# Irrigatron.net
KiCad netlist of a schematic drawn in EasyEDA
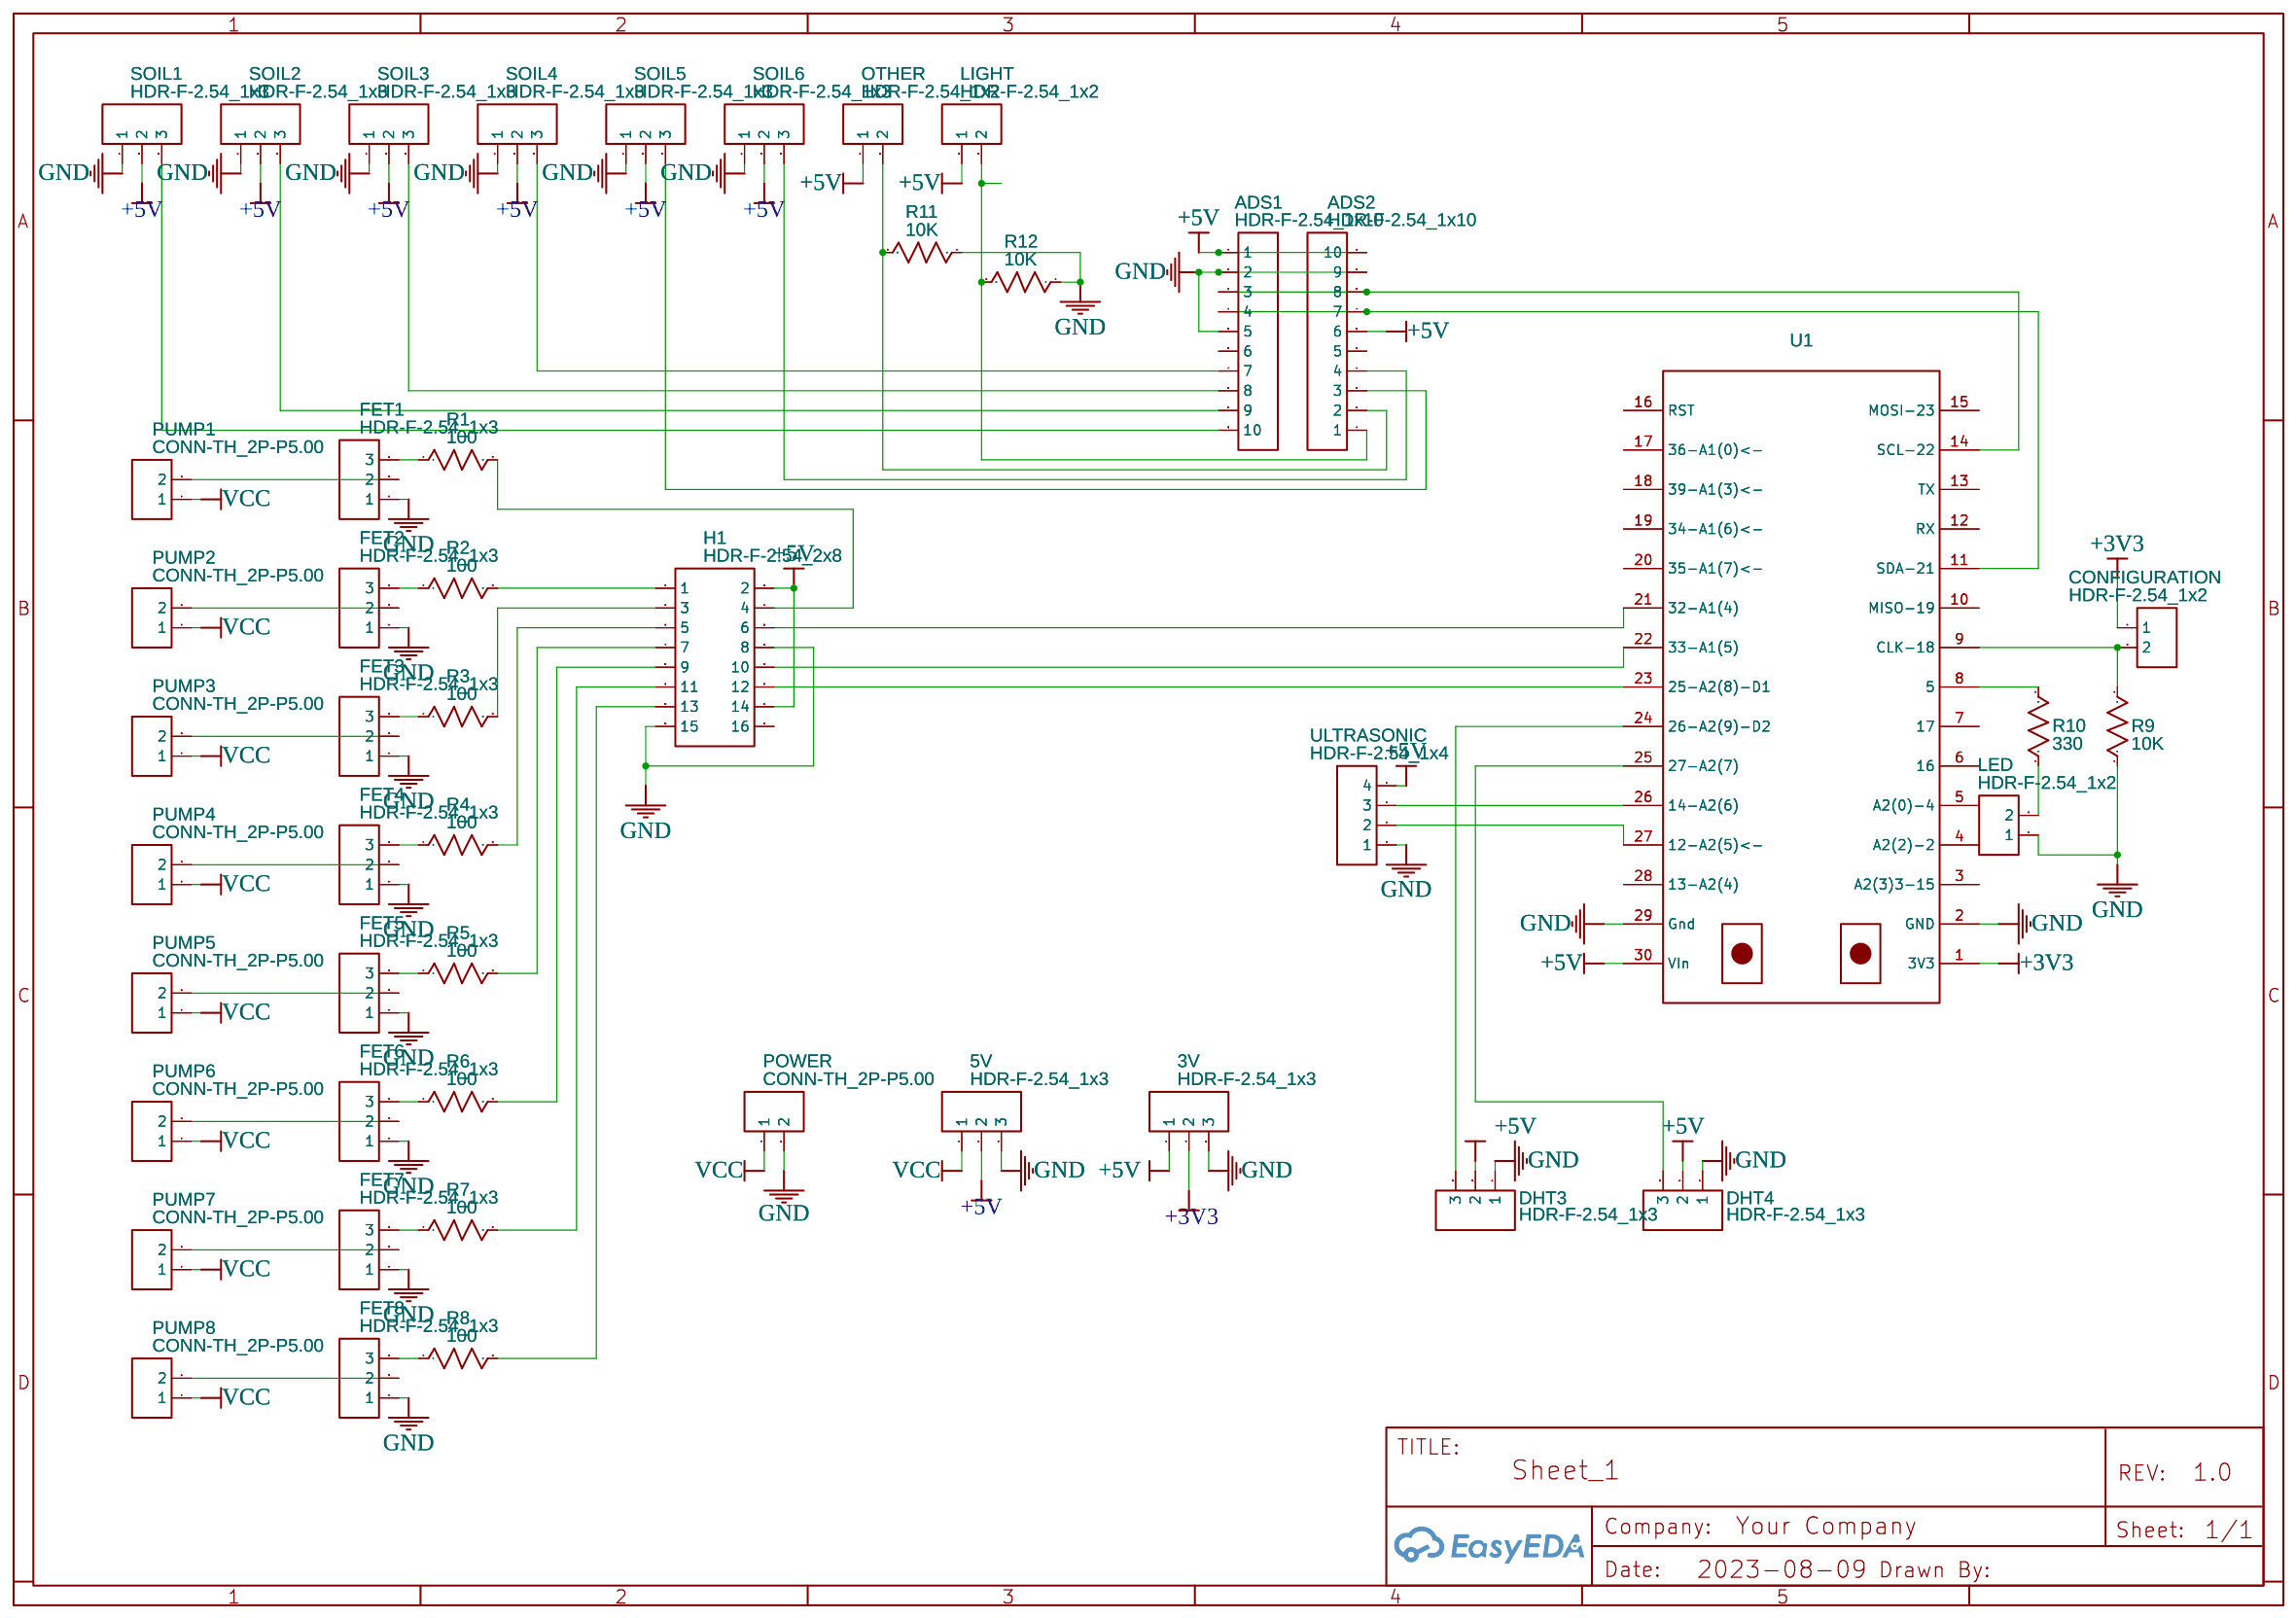
[diagram p0: schematic sheet]

(export (version "E")
  (design (tool "Eeschema 10.0.6"))
  (components
    (comp (ref "3V") (value "HDR-F-2.54_1x3") (libsource (lib "") (part "HDR-F-2.54_1x3_4")))
    (comp (ref "5V") (value "HDR-F-2.54_1x3") (libsource (lib "") (part "HDR-F-2.54_1x3_2")))
    (comp (ref "ADS1") (value "HDR-F-2.54_1x10") (libsource (lib "") (part "HDR-F-2.54_1x10_1")))
    (comp (ref "ADS2") (value "HDR-F-2.54_1x10") (libsource (lib "") (part "HDR-F-2.54_1x10")))
    (comp (ref "CONFIGURATION") (value "HDR-F-2.54_1x2") (libsource (lib "") (part "HDR-F-2.54_1x2")))
    (comp (ref "DHT3") (value "HDR-F-2.54_1x3") (libsource (lib "") (part "HDR-F-2.54_1x3_3")))
    (comp (ref "DHT4") (value "HDR-F-2.54_1x3") (libsource (lib "") (part "HDR-F-2.54_1x3_3")))
    (comp (ref "FET1") (value "HDR-F-2.54_1x3") (libsource (lib "") (part "HDR-F-2.54_1x3_1")))
    (comp (ref "FET2") (value "HDR-F-2.54_1x3") (libsource (lib "") (part "HDR-F-2.54_1x3_1")))
    (comp (ref "FET3") (value "HDR-F-2.54_1x3") (libsource (lib "") (part "HDR-F-2.54_1x3_1")))
    (comp (ref "FET4") (value "HDR-F-2.54_1x3") (libsource (lib "") (part "HDR-F-2.54_1x3_1")))
    (comp (ref "FET5") (value "HDR-F-2.54_1x3") (libsource (lib "") (part "HDR-F-2.54_1x3_1")))
    (comp (ref "FET6") (value "HDR-F-2.54_1x3") (libsource (lib "") (part "HDR-F-2.54_1x3_1")))
    (comp (ref "FET7") (value "HDR-F-2.54_1x3") (libsource (lib "") (part "HDR-F-2.54_1x3_1")))
    (comp (ref "FET8") (value "HDR-F-2.54_1x3") (libsource (lib "") (part "HDR-F-2.54_1x3_1")))
    (comp (ref "H1") (value "HDR-F-2.54_2x8") (libsource (lib "") (part "HDR-F-2.54_2x8")))
    (comp (ref "LED") (value "HDR-F-2.54_1x2") (libsource (lib "") (part "HDR-F-2.54_1x2_2")))
    (comp (ref "LIGHT") (value "HDR-F-2.54_1x2") (libsource (lib "") (part "HDR-F-2.54_1x2_3")))
    (comp (ref "OTHER") (value "HDR-F-2.54_1x2") (libsource (lib "") (part "HDR-F-2.54_1x2_1")))
    (comp (ref "POWER") (value "CONN-TH_2P-P5.00") (libsource (lib "") (part "CONN-TH_2P-P5.00_1")))
    (comp (ref "PUMP1") (value "CONN-TH_2P-P5.00") (libsource (lib "") (part "CONN-TH_2P-P5.00")))
    (comp (ref "PUMP2") (value "CONN-TH_2P-P5.00") (libsource (lib "") (part "CONN-TH_2P-P5.00")))
    (comp (ref "PUMP3") (value "CONN-TH_2P-P5.00") (libsource (lib "") (part "CONN-TH_2P-P5.00")))
    (comp (ref "PUMP4") (value "CONN-TH_2P-P5.00") (libsource (lib "") (part "CONN-TH_2P-P5.00")))
    (comp (ref "PUMP5") (value "CONN-TH_2P-P5.00") (libsource (lib "") (part "CONN-TH_2P-P5.00")))
    (comp (ref "PUMP6") (value "CONN-TH_2P-P5.00") (libsource (lib "") (part "CONN-TH_2P-P5.00")))
    (comp (ref "PUMP7") (value "CONN-TH_2P-P5.00") (libsource (lib "") (part "CONN-TH_2P-P5.00")))
    (comp (ref "PUMP8") (value "CONN-TH_2P-P5.00") (libsource (lib "") (part "CONN-TH_2P-P5.00")))
    (comp (ref "R1") (value "100") (libsource (lib "") (part "R_0603_US")))
    (comp (ref "R2") (value "100") (libsource (lib "") (part "R_0603_US")))
    (comp (ref "R3") (value "100") (libsource (lib "") (part "R_0603_US")))
    (comp (ref "R4") (value "100") (libsource (lib "") (part "R_0603_US")))
    (comp (ref "R5") (value "100") (libsource (lib "") (part "R_0603_US")))
    (comp (ref "R6") (value "100") (libsource (lib "") (part "R_0603_US")))
    (comp (ref "R7") (value "100") (libsource (lib "") (part "R_0603_US")))
    (comp (ref "R8") (value "100") (libsource (lib "") (part "R_0603_US")))
    (comp (ref "R9") (value "10K") (libsource (lib "") (part "R_0603_US_2")))
    (comp (ref "R10") (value "330") (libsource (lib "") (part "R_0603_US_2")))
    (comp (ref "R11") (value "10K") (libsource (lib "") (part "R_0603_US_1")))
    (comp (ref "R12") (value "10K") (libsource (lib "") (part "R_0603_US_1")))
    (comp (ref "SOIL1") (value "HDR-F-2.54_1x3") (libsource (lib "") (part "HDR-F-2.54_1x3")))
    (comp (ref "SOIL2") (value "HDR-F-2.54_1x3") (libsource (lib "") (part "HDR-F-2.54_1x3")))
    (comp (ref "SOIL3") (value "HDR-F-2.54_1x3") (libsource (lib "") (part "HDR-F-2.54_1x3")))
    (comp (ref "SOIL4") (value "HDR-F-2.54_1x3") (libsource (lib "") (part "HDR-F-2.54_1x3")))
    (comp (ref "SOIL5") (value "HDR-F-2.54_1x3") (libsource (lib "") (part "HDR-F-2.54_1x3")))
    (comp (ref "SOIL6") (value "HDR-F-2.54_1x3") (libsource (lib "") (part "HDR-F-2.54_1x3")))
    (comp (ref "U1") (value "NO") (libsource (lib "") (part "DOIT ESP32 DEVKIT V1 (30pins)")))
    (comp (ref "ULTRASONIC") (value "HDR-F-2.54_1x4") (libsource (lib "") (part "HDR-F-2.54_1x4")))
  )
  (nets
    (net (code "1") (name "+3V3") (class "Default")
      (node (ref "3V") (pin "2") (pinfunction "2_2") (pintype "input"))
      (node (ref "CONFIGURATION") (pin "1") (pinfunction "1_1") (pintype "input"))
      (node (ref "U1") (pin "1") (pinfunction "3V3_1") (pintype "unspecified"))
    )
    (net (code "2") (name "+5V") (class "Default")
      (node (ref "3V") (pin "1") (pinfunction "1_1") (pintype "input"))
      (node (ref "5V") (pin "2") (pinfunction "2_2") (pintype "input"))
      (node (ref "ADS1") (pin "1") (pinfunction "1_1") (pintype "unspecified"))
      (node (ref "ADS2") (pin "10") (pinfunction "10_10") (pintype "unspecified"))
      (node (ref "ADS2") (pin "6") (pinfunction "6_6") (pintype "unspecified"))
      (node (ref "DHT3") (pin "2") (pinfunction "2_2") (pintype "input"))
      (node (ref "DHT4") (pin "2") (pinfunction "2_2") (pintype "input"))
      (node (ref "H1") (pin "14") (pinfunction "14_14") (pintype "input"))
      (node (ref "H1") (pin "2") (pinfunction "2_2") (pintype "input"))
      (node (ref "LIGHT") (pin "1") (pinfunction "1_1") (pintype "input"))
      (node (ref "OTHER") (pin "1") (pinfunction "1_1") (pintype "input"))
      (node (ref "SOIL1") (pin "2") (pinfunction "2_2") (pintype "input"))
      (node (ref "SOIL2") (pin "2") (pinfunction "2_2") (pintype "input"))
      (node (ref "SOIL3") (pin "2") (pinfunction "2_2") (pintype "input"))
      (node (ref "SOIL4") (pin "2") (pinfunction "2_2") (pintype "input"))
      (node (ref "SOIL5") (pin "2") (pinfunction "2_2") (pintype "input"))
      (node (ref "SOIL6") (pin "2") (pinfunction "2_2") (pintype "input"))
      (node (ref "U1") (pin "30") (pinfunction "VIn_30") (pintype "unspecified"))
      (node (ref "ULTRASONIC") (pin "4") (pinfunction "4_4") (pintype "unspecified"))
    )
    (net (code "3") (name "GND") (class "Default")
      (node (ref "3V") (pin "3") (pinfunction "3_3") (pintype "input"))
      (node (ref "5V") (pin "3") (pinfunction "3_3") (pintype "input"))
      (node (ref "ADS1") (pin "2") (pinfunction "2_2") (pintype "unspecified"))
      (node (ref "ADS1") (pin "5") (pinfunction "5_5") (pintype "unspecified"))
      (node (ref "ADS2") (pin "9") (pinfunction "9_9") (pintype "unspecified"))
      (node (ref "DHT3") (pin "1") (pinfunction "1_1") (pintype "input"))
      (node (ref "DHT4") (pin "1") (pinfunction "1_1") (pintype "input"))
      (node (ref "FET1") (pin "1") (pinfunction "1_1") (pintype "input"))
      (node (ref "FET2") (pin "1") (pinfunction "1_1") (pintype "input"))
      (node (ref "FET3") (pin "1") (pinfunction "1_1") (pintype "input"))
      (node (ref "FET4") (pin "1") (pinfunction "1_1") (pintype "input"))
      (node (ref "FET5") (pin "1") (pinfunction "1_1") (pintype "input"))
      (node (ref "FET6") (pin "1") (pinfunction "1_1") (pintype "input"))
      (node (ref "FET7") (pin "1") (pinfunction "1_1") (pintype "input"))
      (node (ref "FET8") (pin "1") (pinfunction "1_1") (pintype "input"))
      (node (ref "H1") (pin "15") (pinfunction "15_15") (pintype "input"))
      (node (ref "H1") (pin "8") (pinfunction "8_8") (pintype "input"))
      (node (ref "LED") (pin "1") (pinfunction "1_1") (pintype "input"))
      (node (ref "POWER") (pin "2") (pinfunction "2_2") (pintype "unspecified"))
      (node (ref "R11") (pin "1") (pinfunction "1_1") (pintype "unspecified"))
      (node (ref "R12") (pin "1") (pinfunction "1_1") (pintype "unspecified"))
      (node (ref "R9") (pin "1") (pinfunction "1_1") (pintype "unspecified"))
      (node (ref "SOIL1") (pin "1") (pinfunction "1_1") (pintype "input"))
      (node (ref "SOIL2") (pin "1") (pinfunction "1_1") (pintype "input"))
      (node (ref "SOIL3") (pin "1") (pinfunction "1_1") (pintype "input"))
      (node (ref "SOIL4") (pin "1") (pinfunction "1_1") (pintype "input"))
      (node (ref "SOIL5") (pin "1") (pinfunction "1_1") (pintype "input"))
      (node (ref "SOIL6") (pin "1") (pinfunction "1_1") (pintype "input"))
      (node (ref "U1") (pin "2") (pinfunction "GND_2") (pintype "unspecified"))
      (node (ref "U1") (pin "29") (pinfunction "Gnd_29") (pintype "unspecified"))
      (node (ref "ULTRASONIC") (pin "1") (pinfunction "1_1") (pintype "unspecified"))
    )
    (net (code "4") (name "Net-(ADS1-Pad7)") (class "Default")
      (node (ref "ADS1") (pin "7") (pinfunction "7_7") (pintype "unspecified"))
      (node (ref "SOIL4") (pin "3") (pinfunction "3_3") (pintype "input"))
    )
    (net (code "5") (name "Net-(ADS1-Pad8)") (class "Default")
      (node (ref "ADS1") (pin "8") (pinfunction "8_8") (pintype "unspecified"))
      (node (ref "SOIL3") (pin "3") (pinfunction "3_3") (pintype "input"))
    )
    (net (code "6") (name "Net-(ADS1-Pad9)") (class "Default")
      (node (ref "ADS1") (pin "9") (pinfunction "9_9") (pintype "unspecified"))
      (node (ref "SOIL2") (pin "3") (pinfunction "3_3") (pintype "input"))
    )
    (net (code "7") (name "Net-(ADS1-Pad10)") (class "Default")
      (node (ref "ADS1") (pin "10") (pinfunction "10_10") (pintype "unspecified"))
      (node (ref "SOIL1") (pin "3") (pinfunction "3_3") (pintype "input"))
    )
    (net (code "8") (name "Net-(ADS2-Pad1)") (class "Default")
      (node (ref "ADS2") (pin "1") (pinfunction "1_1") (pintype "unspecified"))
      (node (ref "LIGHT") (pin "2") (pinfunction "2_2") (pintype "input"))
      (node (ref "R12") (pin "2") (pinfunction "2_2") (pintype "unspecified"))
    )
    (net (code "9") (name "Net-(ADS2-Pad2)") (class "Default")
      (node (ref "ADS2") (pin "2") (pinfunction "2_2") (pintype "unspecified"))
      (node (ref "OTHER") (pin "2") (pinfunction "2_2") (pintype "input"))
      (node (ref "R11") (pin "2") (pinfunction "2_2") (pintype "unspecified"))
    )
    (net (code "10") (name "Net-(ADS2-Pad3)") (class "Default")
      (node (ref "ADS2") (pin "3") (pinfunction "3_3") (pintype "unspecified"))
      (node (ref "SOIL5") (pin "3") (pinfunction "3_3") (pintype "input"))
    )
    (net (code "11") (name "Net-(ADS2-Pad4)") (class "Default")
      (node (ref "ADS2") (pin "4") (pinfunction "4_4") (pintype "unspecified"))
      (node (ref "SOIL6") (pin "3") (pinfunction "3_3") (pintype "input"))
    )
    (net (code "12") (name "Net-(FET1-Pad2)") (class "Default")
      (node (ref "FET1") (pin "2") (pinfunction "2_2") (pintype "input"))
      (node (ref "PUMP1") (pin "2") (pinfunction "2_2") (pintype "unspecified"))
    )
    (net (code "13") (name "Net-(FET1-Pad3)") (class "Default")
      (node (ref "FET1") (pin "3") (pinfunction "3_3") (pintype "input"))
      (node (ref "R1") (pin "1") (pinfunction "1_1") (pintype "unspecified"))
    )
    (net (code "14") (name "Net-(FET2-Pad2)") (class "Default")
      (node (ref "FET2") (pin "2") (pinfunction "2_2") (pintype "input"))
      (node (ref "PUMP2") (pin "2") (pinfunction "2_2") (pintype "unspecified"))
    )
    (net (code "15") (name "Net-(FET2-Pad3)") (class "Default")
      (node (ref "FET2") (pin "3") (pinfunction "3_3") (pintype "input"))
      (node (ref "R2") (pin "1") (pinfunction "1_1") (pintype "unspecified"))
    )
    (net (code "16") (name "Net-(FET3-Pad2)") (class "Default")
      (node (ref "FET3") (pin "2") (pinfunction "2_2") (pintype "input"))
      (node (ref "PUMP3") (pin "2") (pinfunction "2_2") (pintype "unspecified"))
    )
    (net (code "17") (name "Net-(FET3-Pad3)") (class "Default")
      (node (ref "FET3") (pin "3") (pinfunction "3_3") (pintype "input"))
      (node (ref "R3") (pin "1") (pinfunction "1_1") (pintype "unspecified"))
    )
    (net (code "18") (name "Net-(FET4-Pad2)") (class "Default")
      (node (ref "FET4") (pin "2") (pinfunction "2_2") (pintype "input"))
      (node (ref "PUMP4") (pin "2") (pinfunction "2_2") (pintype "unspecified"))
    )
    (net (code "19") (name "Net-(FET4-Pad3)") (class "Default")
      (node (ref "FET4") (pin "3") (pinfunction "3_3") (pintype "input"))
      (node (ref "R4") (pin "1") (pinfunction "1_1") (pintype "unspecified"))
    )
    (net (code "20") (name "Net-(FET5-Pad2)") (class "Default")
      (node (ref "FET5") (pin "2") (pinfunction "2_2") (pintype "input"))
      (node (ref "PUMP5") (pin "2") (pinfunction "2_2") (pintype "unspecified"))
    )
    (net (code "21") (name "Net-(FET5-Pad3)") (class "Default")
      (node (ref "FET5") (pin "3") (pinfunction "3_3") (pintype "input"))
      (node (ref "R5") (pin "1") (pinfunction "1_1") (pintype "unspecified"))
    )
    (net (code "22") (name "Net-(FET6-Pad2)") (class "Default")
      (node (ref "FET6") (pin "2") (pinfunction "2_2") (pintype "input"))
      (node (ref "PUMP6") (pin "2") (pinfunction "2_2") (pintype "unspecified"))
    )
    (net (code "23") (name "Net-(FET6-Pad3)") (class "Default")
      (node (ref "FET6") (pin "3") (pinfunction "3_3") (pintype "input"))
      (node (ref "R6") (pin "1") (pinfunction "1_1") (pintype "unspecified"))
    )
    (net (code "24") (name "Net-(FET7-Pad2)") (class "Default")
      (node (ref "FET7") (pin "2") (pinfunction "2_2") (pintype "input"))
      (node (ref "PUMP7") (pin "2") (pinfunction "2_2") (pintype "unspecified"))
    )
    (net (code "25") (name "Net-(FET7-Pad3)") (class "Default")
      (node (ref "FET7") (pin "3") (pinfunction "3_3") (pintype "input"))
      (node (ref "R7") (pin "1") (pinfunction "1_1") (pintype "unspecified"))
    )
    (net (code "26") (name "Net-(FET8-Pad2)") (class "Default")
      (node (ref "FET8") (pin "2") (pinfunction "2_2") (pintype "input"))
      (node (ref "PUMP8") (pin "2") (pinfunction "2_2") (pintype "unspecified"))
    )
    (net (code "27") (name "Net-(FET8-Pad3)") (class "Default")
      (node (ref "FET8") (pin "3") (pinfunction "3_3") (pintype "input"))
      (node (ref "R8") (pin "1") (pinfunction "1_1") (pintype "unspecified"))
    )
    (net (code "28") (name "Net-(H1-Pad1)") (class "Default")
      (node (ref "H1") (pin "1") (pinfunction "1_1") (pintype "input"))
      (node (ref "R2") (pin "2") (pinfunction "2_2") (pintype "unspecified"))
    )
    (net (code "29") (name "Net-(H1-Pad3)") (class "Default")
      (node (ref "H1") (pin "3") (pinfunction "3_3") (pintype "input"))
      (node (ref "R3") (pin "2") (pinfunction "2_2") (pintype "unspecified"))
    )
    (net (code "30") (name "Net-(H1-Pad4)") (class "Default")
      (node (ref "H1") (pin "4") (pinfunction "4_4") (pintype "input"))
      (node (ref "R1") (pin "2") (pinfunction "2_2") (pintype "unspecified"))
    )
    (net (code "31") (name "Net-(H1-Pad5)") (class "Default")
      (node (ref "H1") (pin "5") (pinfunction "5_5") (pintype "input"))
      (node (ref "R4") (pin "2") (pinfunction "2_2") (pintype "unspecified"))
    )
    (net (code "32") (name "Net-(H1-Pad7)") (class "Default")
      (node (ref "H1") (pin "7") (pinfunction "7_7") (pintype "input"))
      (node (ref "R5") (pin "2") (pinfunction "2_2") (pintype "unspecified"))
    )
    (net (code "33") (name "Net-(H1-Pad9)") (class "Default")
      (node (ref "H1") (pin "9") (pinfunction "9_9") (pintype "input"))
      (node (ref "R6") (pin "2") (pinfunction "2_2") (pintype "unspecified"))
    )
    (net (code "34") (name "Net-(H1-Pad11)") (class "Default")
      (node (ref "H1") (pin "11") (pinfunction "11_11") (pintype "input"))
      (node (ref "R7") (pin "2") (pinfunction "2_2") (pintype "unspecified"))
    )
    (net (code "35") (name "Net-(H1-Pad13)") (class "Default")
      (node (ref "H1") (pin "13") (pinfunction "13_13") (pintype "input"))
      (node (ref "R8") (pin "2") (pinfunction "2_2") (pintype "unspecified"))
    )
    (net (code "36") (name "Net-(LED-Pad2)") (class "Default")
      (node (ref "LED") (pin "2") (pinfunction "2_2") (pintype "input"))
      (node (ref "R10") (pin "1") (pinfunction "1_1") (pintype "unspecified"))
    )
    (net (code "37") (name "Net-(U1-5)") (class "Default")
      (node (ref "R10") (pin "2") (pinfunction "2_2") (pintype "unspecified"))
      (node (ref "U1") (pin "8") (pinfunction "5_8") (pintype "unspecified"))
    )
    (net (code "38") (name "Net-(U1-12-A2(5)<-)") (class "Default")
      (node (ref "U1") (pin "27") (pinfunction "12-A2(5)<-_27") (pintype "unspecified"))
      (node (ref "ULTRASONIC") (pin "2") (pinfunction "2_2") (pintype "unspecified"))
    )
    (net (code "39") (name "Net-(U1-14-A2(6))") (class "Default")
      (node (ref "U1") (pin "26") (pinfunction "14-A2(6)_26") (pintype "unspecified"))
      (node (ref "ULTRASONIC") (pin "3") (pinfunction "3_3") (pintype "unspecified"))
    )
    (net (code "40") (name "Net-(U1-25-A2(8)-D1)") (class "Default")
      (node (ref "H1") (pin "12") (pinfunction "12_12") (pintype "input"))
      (node (ref "U1") (pin "23") (pinfunction "25-A2(8)-D1_23") (pintype "unspecified"))
    )
    (net (code "41") (name "Net-(U1-26-A2(9)-D2)") (class "Default")
      (node (ref "DHT3") (pin "3") (pinfunction "3_3") (pintype "input"))
      (node (ref "U1") (pin "24") (pinfunction "26-A2(9)-D2_24") (pintype "unspecified"))
    )
    (net (code "42") (name "Net-(U1-27-A2(7))") (class "Default")
      (node (ref "DHT4") (pin "3") (pinfunction "3_3") (pintype "input"))
      (node (ref "U1") (pin "25") (pinfunction "27-A2(7)_25") (pintype "unspecified"))
    )
    (net (code "43") (name "Net-(U1-32-A1(4))") (class "Default")
      (node (ref "H1") (pin "6") (pinfunction "6_6") (pintype "input"))
      (node (ref "U1") (pin "21") (pinfunction "32-A1(4)_21") (pintype "unspecified"))
    )
    (net (code "44") (name "Net-(U1-33-A1(5))") (class "Default")
      (node (ref "H1") (pin "10") (pinfunction "10_10") (pintype "input"))
      (node (ref "U1") (pin "22") (pinfunction "33-A1(5)_22") (pintype "unspecified"))
    )
    (net (code "45") (name "Net-(U1-CLK-18)") (class "Default")
      (node (ref "CONFIGURATION") (pin "2") (pinfunction "2_2") (pintype "input"))
      (node (ref "R9") (pin "2") (pinfunction "2_2") (pintype "unspecified"))
      (node (ref "U1") (pin "9") (pinfunction "CLK-18_9") (pintype "unspecified"))
    )
    (net (code "46") (name "Net-(U1-SCL-22)") (class "Default")
      (node (ref "ADS1") (pin "3") (pinfunction "3_3") (pintype "unspecified"))
      (node (ref "ADS2") (pin "8") (pinfunction "8_8") (pintype "unspecified"))
      (node (ref "U1") (pin "14") (pinfunction "SCL-22_14") (pintype "unspecified"))
    )
    (net (code "47") (name "Net-(U1-SDA-21)") (class "Default")
      (node (ref "ADS1") (pin "4") (pinfunction "4_4") (pintype "unspecified"))
      (node (ref "ADS2") (pin "7") (pinfunction "7_7") (pintype "unspecified"))
      (node (ref "U1") (pin "11") (pinfunction "SDA-21_11") (pintype "unspecified"))
    )
    (net (code "48") (name "VCC") (class "Default")
      (node (ref "5V") (pin "1") (pinfunction "1_1") (pintype "input"))
      (node (ref "POWER") (pin "1") (pinfunction "1_1") (pintype "unspecified"))
      (node (ref "PUMP1") (pin "1") (pinfunction "1_1") (pintype "unspecified"))
      (node (ref "PUMP2") (pin "1") (pinfunction "1_1") (pintype "unspecified"))
      (node (ref "PUMP3") (pin "1") (pinfunction "1_1") (pintype "unspecified"))
      (node (ref "PUMP4") (pin "1") (pinfunction "1_1") (pintype "unspecified"))
      (node (ref "PUMP5") (pin "1") (pinfunction "1_1") (pintype "unspecified"))
      (node (ref "PUMP6") (pin "1") (pinfunction "1_1") (pintype "unspecified"))
      (node (ref "PUMP7") (pin "1") (pinfunction "1_1") (pintype "unspecified"))
      (node (ref "PUMP8") (pin "1") (pinfunction "1_1") (pintype "unspecified"))
    )
    (net (code "49") (name "unconnected-(ADS1-Pad6)") (class "Default")
      (node (ref "ADS1") (pin "6") (pinfunction "6_6") (pintype "unspecified"))
    )
    (net (code "50") (name "unconnected-(ADS2-Pad5)") (class "Default")
      (node (ref "ADS2") (pin "5") (pinfunction "5_5") (pintype "unspecified"))
    )
    (net (code "51") (name "unconnected-(H1-Pad16)") (class "Default")
      (node (ref "H1") (pin "16") (pinfunction "16_16") (pintype "input"))
    )
    (net (code "52") (name "unconnected-(U1-13-A2(4)-Pad28)") (class "Default")
      (node (ref "U1") (pin "28") (pinfunction "13-A2(4)_28") (pintype "unspecified"))
    )
    (net (code "53") (name "unconnected-(U1-16-Pad6)") (class "Default")
      (node (ref "U1") (pin "6") (pinfunction "16_6") (pintype "unspecified"))
    )
    (net (code "54") (name "unconnected-(U1-17-Pad7)") (class "Default")
      (node (ref "U1") (pin "7") (pinfunction "17_7") (pintype "unspecified"))
    )
    (net (code "55") (name "unconnected-(U1-34-A1(6)<--Pad19)") (class "Default")
      (node (ref "U1") (pin "19") (pinfunction "34-A1(6)<-_19") (pintype "unspecified"))
    )
    (net (code "56") (name "unconnected-(U1-35-A1(7)<--Pad20)") (class "Default")
      (node (ref "U1") (pin "20") (pinfunction "35-A1(7)<-_20") (pintype "unspecified"))
    )
    (net (code "57") (name "unconnected-(U1-36-A1(0)<--Pad17)") (class "Default")
      (node (ref "U1") (pin "17") (pinfunction "36-A1(0)<-_17") (pintype "unspecified"))
    )
    (net (code "58") (name "unconnected-(U1-39-A1(3)<--Pad18)") (class "Default")
      (node (ref "U1") (pin "18") (pinfunction "39-A1(3)<-_18") (pintype "unspecified"))
    )
    (net (code "59") (name "unconnected-(U1-A2(0)-4-Pad5)") (class "Default")
      (node (ref "U1") (pin "5") (pinfunction "A2(0)-4_5") (pintype "unspecified"))
    )
    (net (code "60") (name "unconnected-(U1-A2(2)-2-Pad4)") (class "Default")
      (node (ref "U1") (pin "4") (pinfunction "A2(2)-2_4") (pintype "unspecified"))
    )
    (net (code "61") (name "unconnected-(U1-A2(3)3-15-Pad3)") (class "Default")
      (node (ref "U1") (pin "3") (pinfunction "A2(3)3-15_3") (pintype "unspecified"))
    )
    (net (code "62") (name "unconnected-(U1-MISO-19-Pad10)") (class "Default")
      (node (ref "U1") (pin "10") (pinfunction "MISO-19_10") (pintype "unspecified"))
    )
    (net (code "63") (name "unconnected-(U1-MOSI-23-Pad15)") (class "Default")
      (node (ref "U1") (pin "15") (pinfunction "MOSI-23_15") (pintype "unspecified"))
    )
    (net (code "64") (name "unconnected-(U1-RST-Pad16)") (class "Default")
      (node (ref "U1") (pin "16") (pinfunction "RST_16") (pintype "unspecified"))
    )
    (net (code "65") (name "unconnected-(U1-RX-Pad12)") (class "Default")
      (node (ref "U1") (pin "12") (pinfunction "RX_12") (pintype "unspecified"))
    )
    (net (code "66") (name "unconnected-(U1-TX-Pad13)") (class "Default")
      (node (ref "U1") (pin "13") (pinfunction "TX_13") (pintype "unspecified"))
    )
  )
)
